# x9d_usb-c_mod.net
KiCad netlist of a schematic drawn in EAGLE
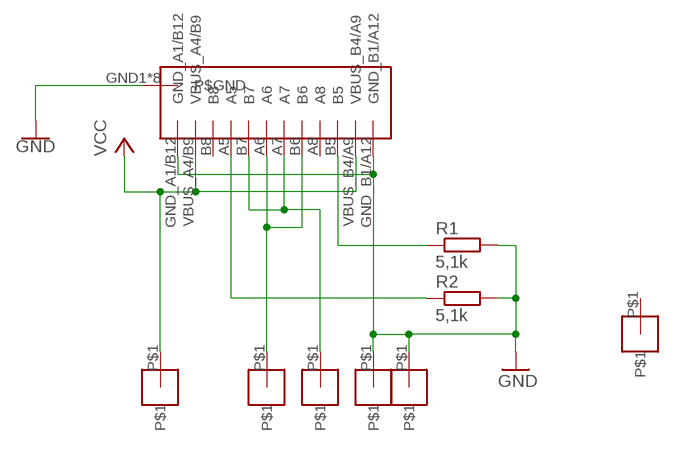
[diagram p0: schematic, sheet 1]

(export (version "E")
  (design (tool "Eeschema 10.0.6"))
  (components
    (comp (ref "GND1")
      (value "MOTORPADPAD_1X2")
      (footprint "eagle-import:PAD_1X2")
      (libsource (lib "eagle-import") (part "MOTORPADPAD_1X2"))
    )
    (comp (ref "MID1")
      (value "MOTORPADPAD_1X2")
      (footprint "eagle-import:PAD_1X2")
      (libsource (lib "eagle-import") (part "MOTORPADPAD_1X2"))
    )
    (comp (ref "MID2")
      (value "MOTORPADPAD_1X2")
      (footprint "eagle-import:PAD_1X2")
      (libsource (lib "eagle-import") (part "MOTORPADPAD_1X2"))
    )
    (comp (ref "MID3")
      (value "MOTORPADPAD_1X2")
      (footprint "eagle-import:PAD_1X2")
      (libsource (lib "eagle-import") (part "MOTORPADPAD_1X2"))
    )
    (comp (ref "MID4")
      (value "MOTORPADPAD_1X2")
      (footprint "eagle-import:PAD_1X2")
      (libsource (lib "eagle-import") (part "MOTORPADPAD_1X2"))
    )
    (comp (ref "MID6")
      (value "MOTORPADPAD_1X2")
      (footprint "eagle-import:PAD_1X2")
      (libsource (lib "eagle-import") (part "MOTORPADPAD_1X2"))
    )
    (comp (ref "R1")
      (value "5,1k")
      (footprint "eagle-import:R0805")
      (libsource (lib "eagle-import") (part "R-EU_R0805"))
    )
    (comp (ref "R2")
      (value "5,1k")
      (footprint "eagle-import:R0805")
      (libsource (lib "eagle-import") (part "R-EU_R0805"))
    )
    (comp (ref "U$1")
      (value "USB-C_2.0SOFNG_MC-331D")
      (footprint "eagle-import:USB-C_MC-331D")
      (libsource (lib "eagle-import") (part "USB-C_2.0SOFNG_MC-331D"))
    )
  )
  (nets
    (net (code "1") (name "GND") (class "Default")
      (node (ref "GND1") (pin "P$1") (pinfunction "P$1_P$1") (pintype "bidirectional"))
      (node (ref "MID1") (pin "P$1") (pinfunction "P$1_P$1") (pintype "bidirectional"))
      (node (ref "R1") (pin "2") (pinfunction "2_2") (pintype "passive"))
      (node (ref "R2") (pin "2") (pinfunction "2_2") (pintype "passive"))
      (node (ref "U$1") (pin "GND1") (pinfunction "P$GND_GND1") (pintype "bidirectional"))
      (node (ref "U$1") (pin "GND2") (pinfunction "P$GND_GND2") (pintype "bidirectional"))
      (node (ref "U$1") (pin "GND3") (pinfunction "P$GND_GND3") (pintype "bidirectional"))
      (node (ref "U$1") (pin "GND4") (pinfunction "P$GND_GND4") (pintype "bidirectional"))
      (node (ref "U$1") (pin "GND5") (pinfunction "P$GND_GND5") (pintype "bidirectional"))
      (node (ref "U$1") (pin "GND6") (pinfunction "P$GND_GND6") (pintype "bidirectional"))
      (node (ref "U$1") (pin "GND7") (pinfunction "P$GND_GND7") (pintype "bidirectional"))
      (node (ref "U$1") (pin "GND8") (pinfunction "P$GND_GND8") (pintype "bidirectional"))
      (node (ref "U$1") (pin "GND_A1/B12") (pinfunction "GND_A1/B12_GND_A1/B12") (pintype "bidirectional"))
      (node (ref "U$1") (pin "GND_B1/A12") (pinfunction "GND_B1/A12_GND_B1/A12") (pintype "bidirectional"))
    )
    (net (code "2") (name "Net-(MID3-PadP$1)") (class "Default")
      (node (ref "MID3") (pin "P$1") (pinfunction "P$1_P$1") (pintype "bidirectional"))
      (node (ref "U$1") (pin "A6") (pinfunction "A6_A6") (pintype "bidirectional"))
      (node (ref "U$1") (pin "B6") (pinfunction "B6_B6") (pintype "bidirectional"))
    )
    (net (code "3") (name "Net-(MID6-PadP$1)") (class "Default")
      (node (ref "MID6") (pin "P$1") (pinfunction "P$1_P$1") (pintype "bidirectional"))
      (node (ref "U$1") (pin "A7") (pinfunction "A7_A7") (pintype "bidirectional"))
      (node (ref "U$1") (pin "B7") (pinfunction "B7_B7") (pintype "bidirectional"))
    )
    (net (code "4") (name "Net-(R1-Pad1)") (class "Default")
      (node (ref "R1") (pin "1") (pinfunction "1_1") (pintype "passive"))
      (node (ref "U$1") (pin "B5") (pinfunction "B5_B5") (pintype "bidirectional"))
    )
    (net (code "5") (name "Net-(R2-Pad1)") (class "Default")
      (node (ref "R2") (pin "1") (pinfunction "1_1") (pintype "passive"))
      (node (ref "U$1") (pin "A5") (pinfunction "A5_A5") (pintype "bidirectional"))
    )
    (net (code "6") (name "VCC") (class "Default")
      (node (ref "MID2") (pin "P$1") (pinfunction "P$1_P$1") (pintype "bidirectional"))
      (node (ref "U$1") (pin "VBUS_A4/B9") (pinfunction "VBUS_A4/B9_VBUS_A4/B9") (pintype "bidirectional"))
      (node (ref "U$1") (pin "VBUS_B4/A9") (pinfunction "VBUS_B4/A9_VBUS_B4/A9") (pintype "bidirectional"))
    )
    (net (code "7") (name "unconnected-(MID4-PadP$1)") (class "Default")
      (node (ref "MID4") (pin "P$1") (pinfunction "P$1_P$1") (pintype "bidirectional"))
    )
    (net (code "8") (name "unconnected-(U$1-PadA8)") (class "Default")
      (node (ref "U$1") (pin "A8") (pinfunction "A8_A8") (pintype "bidirectional"))
    )
    (net (code "9") (name "unconnected-(U$1-PadB8)") (class "Default")
      (node (ref "U$1") (pin "B8") (pinfunction "B8_B8") (pintype "bidirectional"))
    )
  )
)
